# VCO-Simple-Back.net
KiCad netlist of a schematic drawn in EAGLE
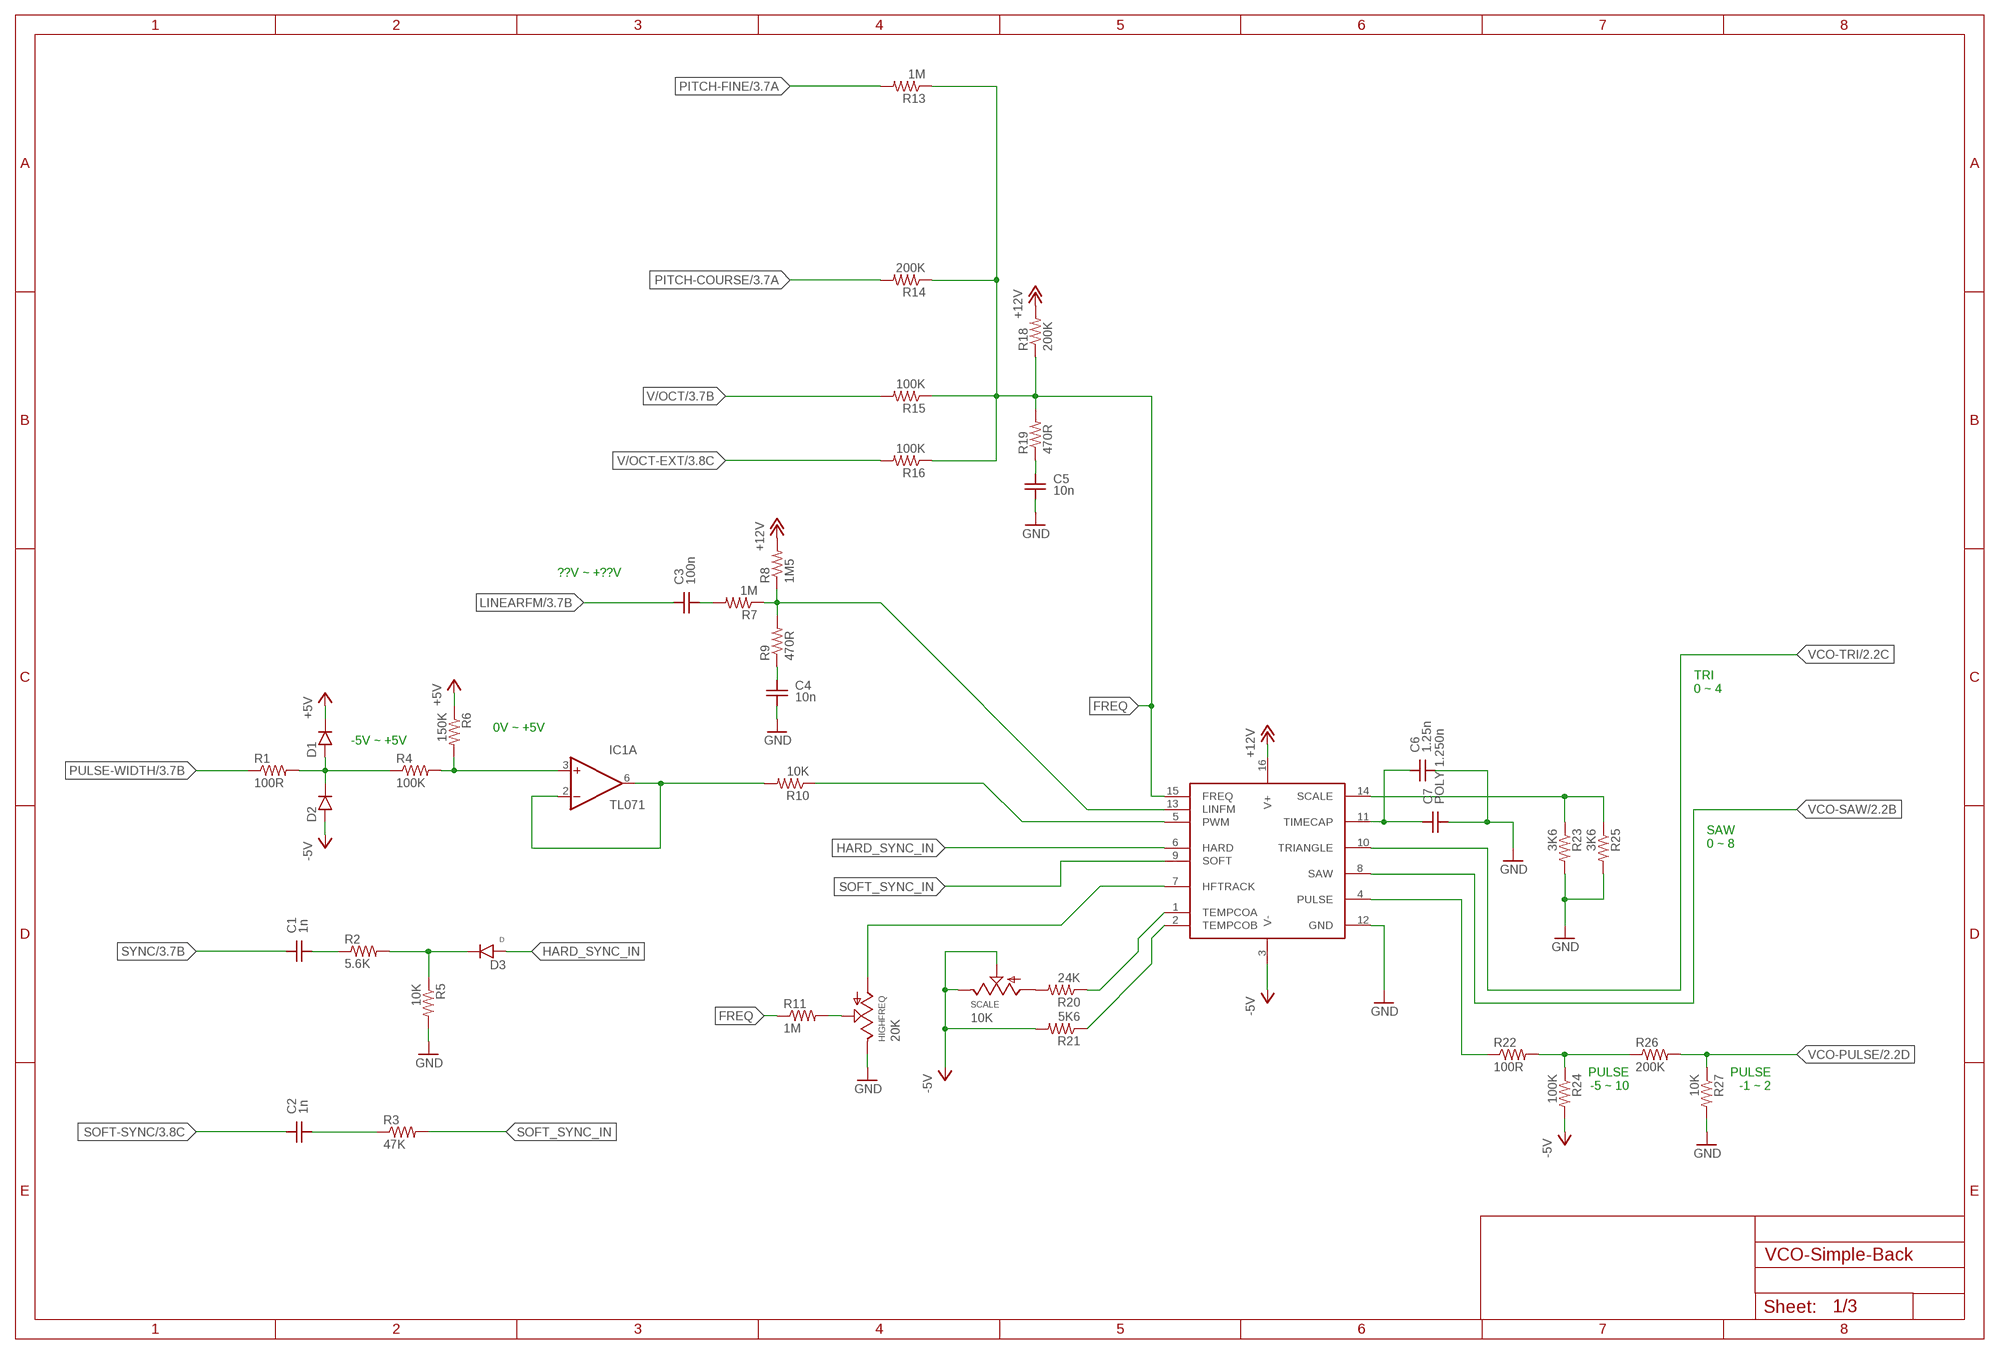
[diagram p0: schematic, sheet 1]
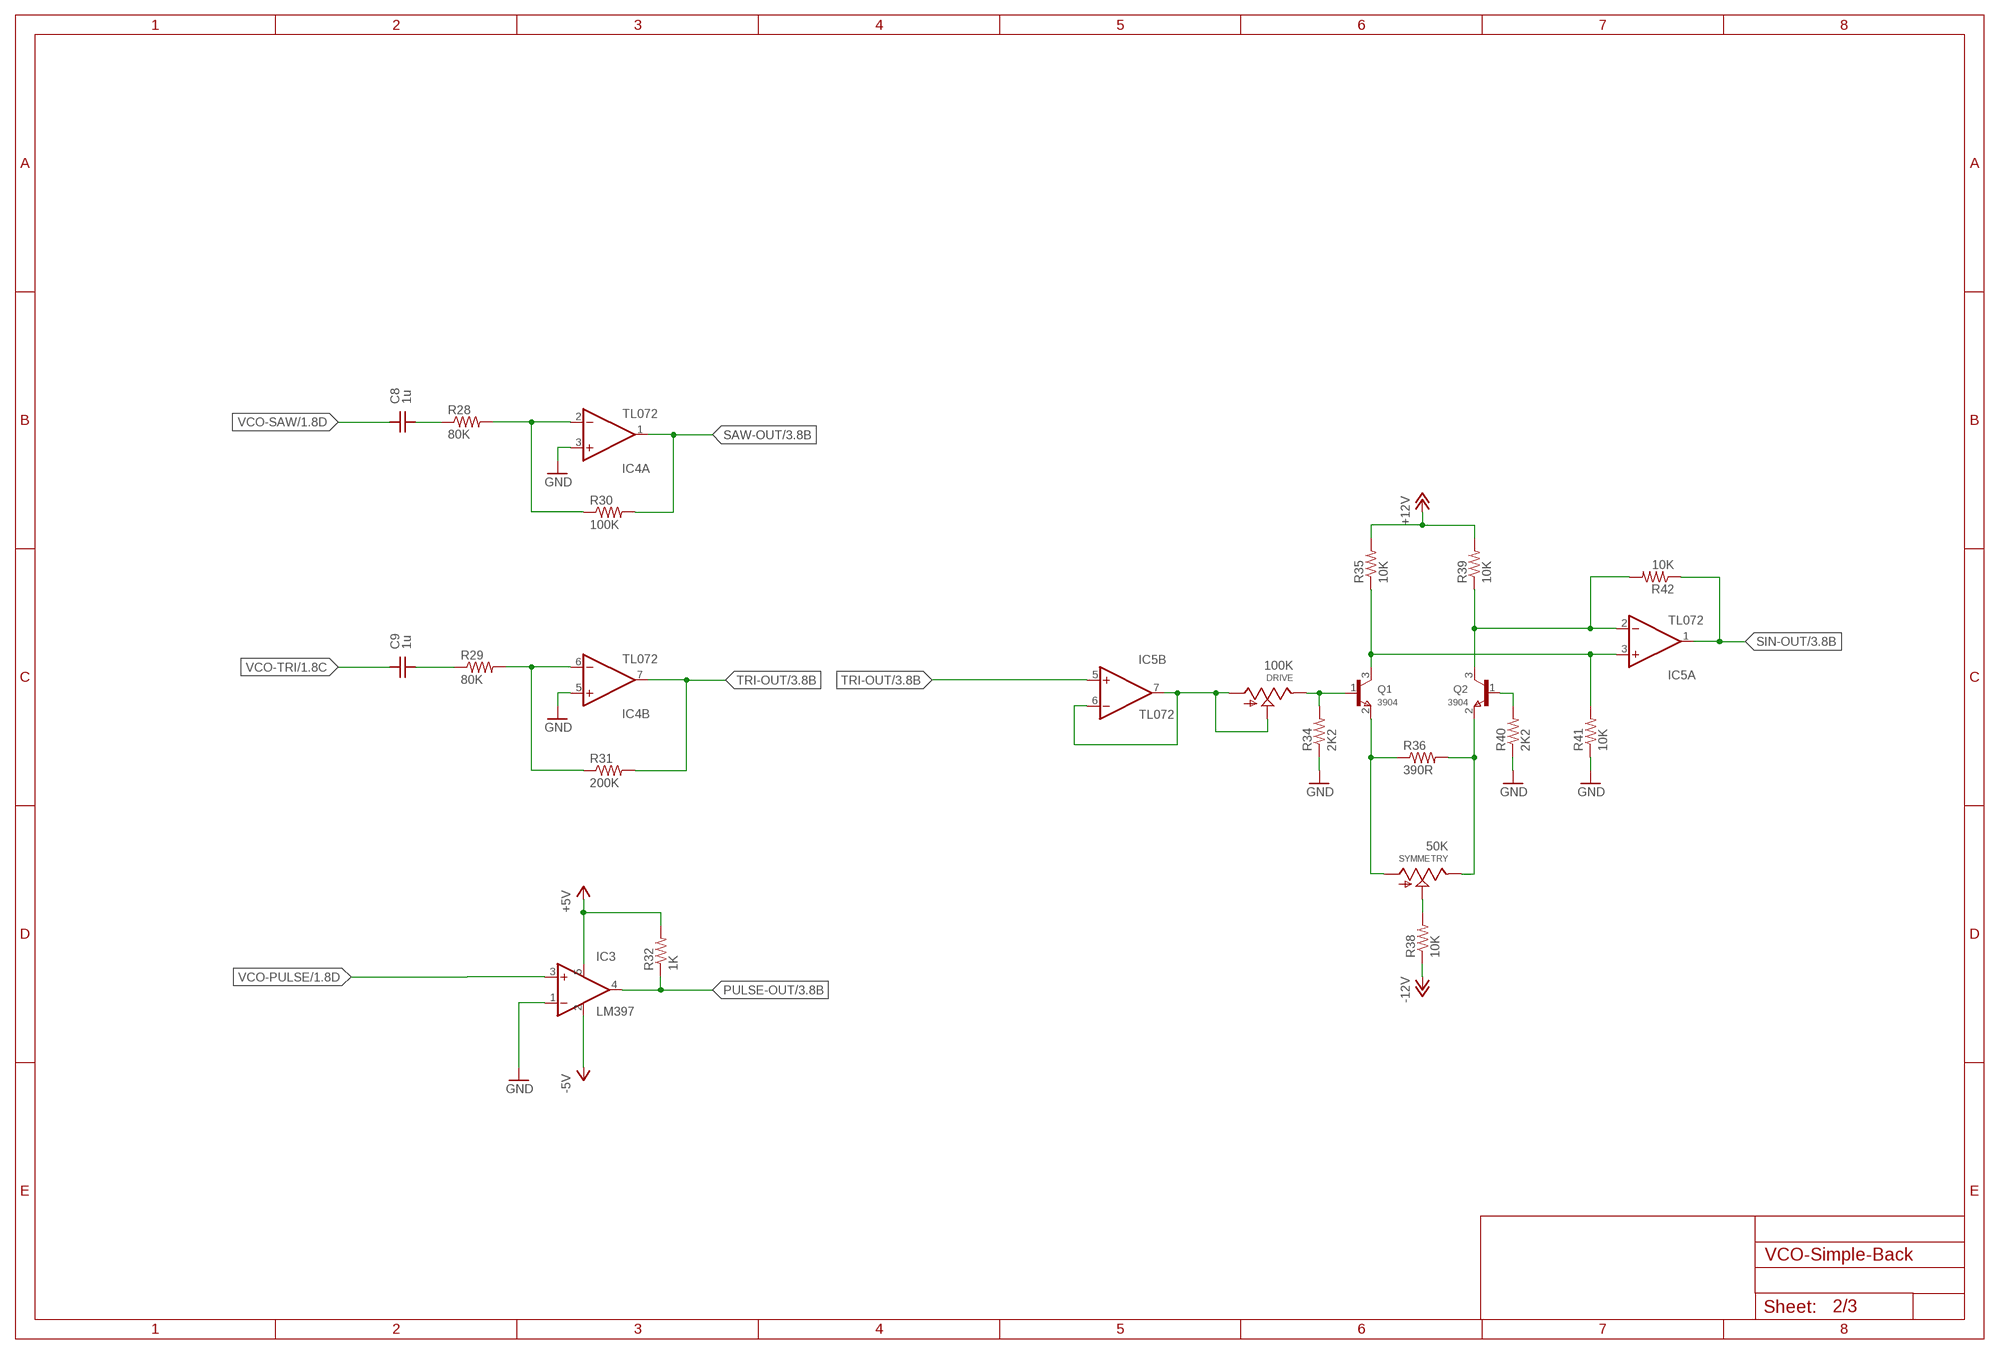
[diagram p1: schematic, sheet 2]
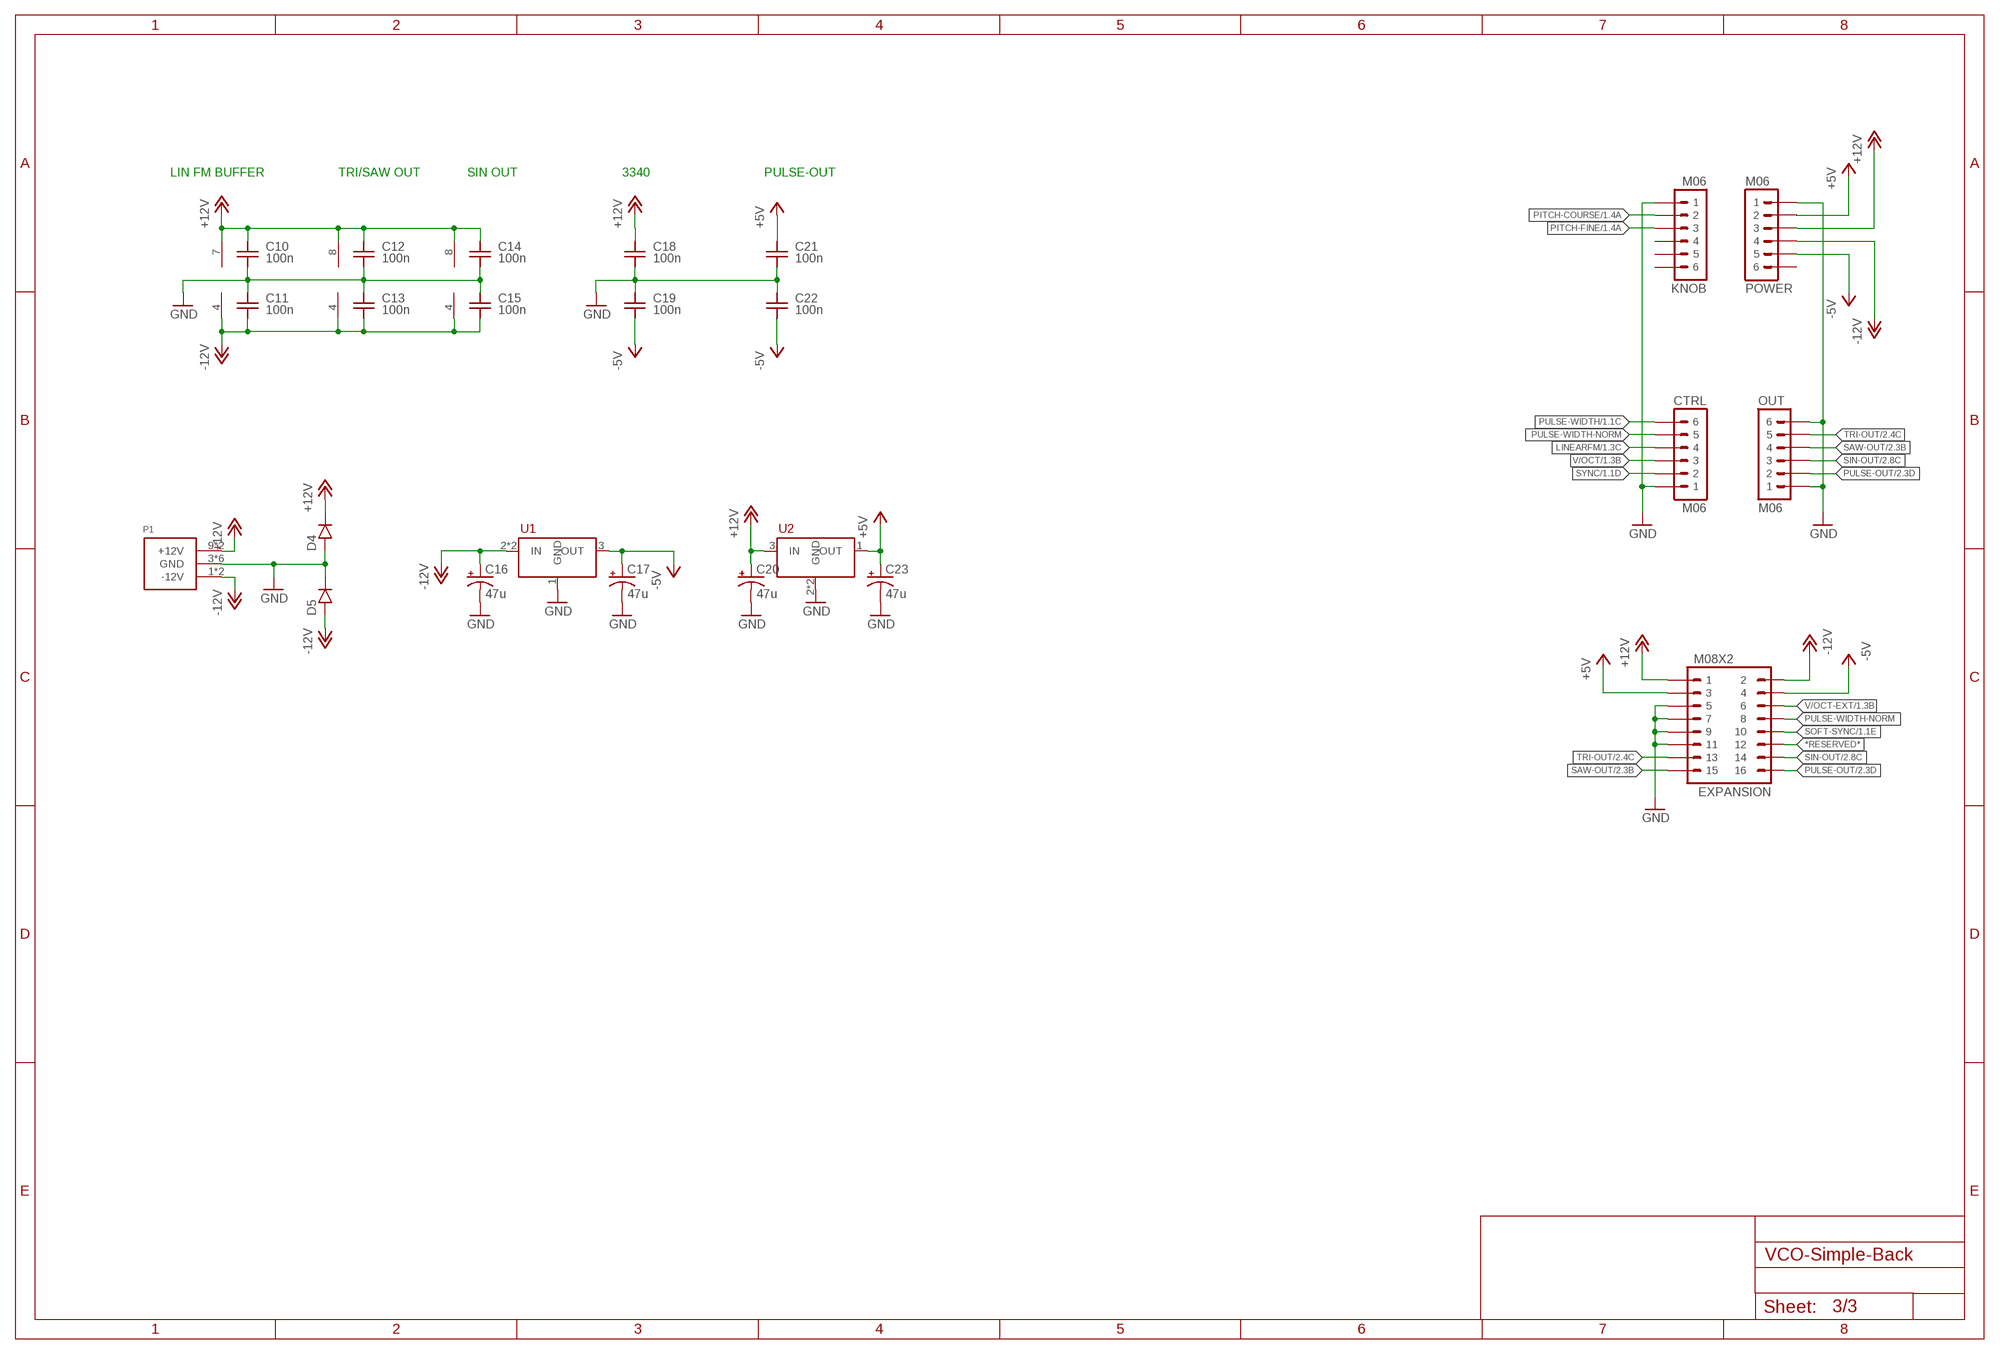
[diagram p2: schematic, sheet 3]

(export (version "E")
  (design (tool "Eeschema 10.0.6"))
  (components
    (comp (ref "C10")
      (value "100n")
      (footprint "eagle-import:C-0805")
      (libsource (lib "eagle-import") (part "CAPACITOR0805"))
    )
    (comp (ref "C11")
      (value "100n")
      (footprint "eagle-import:C-0805")
      (libsource (lib "eagle-import") (part "CAPACITOR0805"))
    )
    (comp (ref "C12")
      (value "100n")
      (footprint "eagle-import:C-0805")
      (libsource (lib "eagle-import") (part "CAPACITOR0805"))
    )
    (comp (ref "C13")
      (value "100n")
      (footprint "eagle-import:C-0805")
      (libsource (lib "eagle-import") (part "CAPACITOR0805"))
    )
    (comp (ref "C14")
      (value "100n")
      (footprint "eagle-import:C-0805")
      (libsource (lib "eagle-import") (part "CAPACITOR0805"))
    )
    (comp (ref "C15")
      (value "100n")
      (footprint "eagle-import:C-0805")
      (libsource (lib "eagle-import") (part "CAPACITOR0805"))
    )
    (comp (ref "C16")
      (value "47u")
      (footprint "eagle-import:PANASONIC_C")
      (libsource (lib "eagle-import") (part "CPOL-USC"))
    )
    (comp (ref "C17")
      (value "47u")
      (footprint "eagle-import:PANASONIC_C")
      (libsource (lib "eagle-import") (part "CPOL-USC"))
    )
    (comp (ref "C18")
      (value "100n")
      (footprint "eagle-import:C-0805")
      (libsource (lib "eagle-import") (part "CAPACITOR0805"))
    )
    (comp (ref "C19")
      (value "100n")
      (footprint "eagle-import:C-0805")
      (libsource (lib "eagle-import") (part "CAPACITOR0805"))
    )
    (comp (ref "C20")
      (value "47u")
      (footprint "eagle-import:PANASONIC_C")
      (libsource (lib "eagle-import") (part "CPOL-USC"))
    )
    (comp (ref "C21")
      (value "100n")
      (footprint "eagle-import:C-0805")
      (libsource (lib "eagle-import") (part "CAPACITOR0805"))
    )
    (comp (ref "C22")
      (value "100n")
      (footprint "eagle-import:C-0805")
      (libsource (lib "eagle-import") (part "CAPACITOR0805"))
    )
    (comp (ref "C23")
      (value "47u")
      (footprint "eagle-import:PANASONIC_C")
      (libsource (lib "eagle-import") (part "CPOL-USC"))
    )
    (comp (ref "CTRL")
      (value "M06")
      (footprint "eagle-import:M06")
      (libsource (lib "eagle-import") (part "M06"))
    )
    (comp (ref "D4")
      (value "DIODESOD-123")
      (footprint "eagle-import:SOD-123")
      (libsource (lib "eagle-import") (part "DIODESOD-123"))
    )
    (comp (ref "D5")
      (value "DIODESOD-123")
      (footprint "eagle-import:SOD-123")
      (libsource (lib "eagle-import") (part "DIODESOD-123"))
    )
    (comp (ref "EXPANSION")
      (value "M08X2")
      (footprint "eagle-import:M08X2")
      (libsource (lib "eagle-import") (part "M08X2"))
    )
    (comp (ref "IC1")
      (value "TL071")
      (footprint "eagle-import:SO08")
      (libsource (lib "eagle-import") (part "OPAMP-SINGLE"))
    )
    (comp (ref "IC4")
      (value "TL072")
      (footprint "eagle-import:SO08")
      (libsource (lib "eagle-import") (part "OPAMP-DUAL"))
    )
    (comp (ref "IC5")
      (value "TL072")
      (footprint "eagle-import:SO08")
      (libsource (lib "eagle-import") (part "OPAMP-DUAL"))
    )
    (comp (ref "KNOB")
      (value "M06")
      (footprint "eagle-import:M06")
      (libsource (lib "eagle-import") (part "M06"))
    )
    (comp (ref "OUT")
      (value "M06")
      (footprint "eagle-import:M06")
      (libsource (lib "eagle-import") (part "M06"))
    )
    (comp (ref "P1")
      (value "POWER_SIMPLE10_SHROUDED")
      (footprint "eagle-import:POWER_10_SHROUDED")
      (libsource (lib "eagle-import") (part "POWER_SIMPLE10_SHROUDED"))
    )
    (comp (ref "POWER")
      (value "M06")
      (footprint "eagle-import:M06")
      (libsource (lib "eagle-import") (part "M06"))
    )
    (comp (ref "U1")
      (value "LM79L05A")
      (footprint "eagle-import:SOT89")
      (libsource (lib "eagle-import") (part "LM79L05A"))
    )
    (comp (ref "U2")
      (value "MC78L05A")
      (footprint "eagle-import:SOT89")
      (libsource (lib "eagle-import") (part "MC78L05A"))
    )
    (comp (ref "C1")
      (value "1n")
      (footprint "eagle-import:C-0805")
      (libsource (lib "eagle-import") (part "CAPACITOR0805"))
    )
    (comp (ref "C2")
      (value "1n")
      (footprint "eagle-import:C-0805")
      (libsource (lib "eagle-import") (part "CAPACITOR0805"))
    )
    (comp (ref "C3")
      (value "100n")
      (footprint "eagle-import:C-0805")
      (libsource (lib "eagle-import") (part "CAPACITOR0805"))
    )
    (comp (ref "C4")
      (value "10n")
      (footprint "eagle-import:C-0805")
      (libsource (lib "eagle-import") (part "CAPACITOR0805"))
    )
    (comp (ref "C5")
      (value "10n")
      (footprint "eagle-import:C-0805")
      (libsource (lib "eagle-import") (part "CAPACITOR0805"))
    )
    (comp (ref "C6")
      (value "1.25n")
      (footprint "eagle-import:C-0805")
      (libsource (lib "eagle-import") (part "CAPACITOR0805"))
    )
    (comp (ref "C7")
      (value "POLY 1.250n")
      (footprint "eagle-import:CAP-5MM")
      (libsource (lib "eagle-import") (part "CAPACITOR5MM"))
    )
    (comp (ref "D1")
      (value "DIODESOD-323")
      (footprint "eagle-import:SOD-323")
      (libsource (lib "eagle-import") (part "DIODESOD-323"))
    )
    (comp (ref "D2")
      (value "DIODESOD-323")
      (footprint "eagle-import:SOD-323")
      (libsource (lib "eagle-import") (part "DIODESOD-323"))
    )
    (comp (ref "D3")
      (value "D")
      (footprint "eagle-import:SOD-323")
      (libsource (lib "eagle-import") (part "DIODESOD-323"))
    )
    (comp (ref "HIGHFREQ")
      (value "20K")
      (footprint "eagle-import:POT-TRIM-MULTI-V")
      (libsource (lib "eagle-import") (part "POTTRIM-MULTITURN-VERT"))
    )
    (comp (ref "IC2")
      (value "V3340SO16")
      (footprint "eagle-import:SO16")
      (libsource (lib "eagle-import") (part "V3340SO16"))
    )
    (comp (ref "R1")
      (value "100R")
      (footprint "eagle-import:R-0805-MILL")
      (libsource (lib "eagle-import") (part "RESISTOR0805"))
    )
    (comp (ref "R2")
      (value "5.6K")
      (footprint "eagle-import:R-0805-MILL")
      (libsource (lib "eagle-import") (part "RESISTOR0805"))
    )
    (comp (ref "R3")
      (value "47K")
      (footprint "eagle-import:R-0805-MILL")
      (libsource (lib "eagle-import") (part "RESISTOR0805"))
    )
    (comp (ref "R4")
      (value "100K")
      (footprint "eagle-import:R-0805-MILL")
      (libsource (lib "eagle-import") (part "RESISTOR0805"))
    )
    (comp (ref "R5")
      (value "10K")
      (footprint "eagle-import:R-0805-MILL")
      (libsource (lib "eagle-import") (part "RESISTOR0805"))
    )
    (comp (ref "R6")
      (value "150K")
      (footprint "eagle-import:R-0805-MILL")
      (libsource (lib "eagle-import") (part "RESISTOR0805"))
    )
    (comp (ref "R7")
      (value "1M")
      (footprint "eagle-import:R-0805-MILL")
      (libsource (lib "eagle-import") (part "RESISTOR0805"))
    )
    (comp (ref "R8")
      (value "1M5")
      (footprint "eagle-import:R-0805-MILL")
      (libsource (lib "eagle-import") (part "RESISTOR0805"))
    )
    (comp (ref "R9")
      (value "470R")
      (footprint "eagle-import:R-0805-MILL")
      (libsource (lib "eagle-import") (part "RESISTOR0805"))
    )
    (comp (ref "R10")
      (value "10K")
      (footprint "eagle-import:R-0805-MILL")
      (libsource (lib "eagle-import") (part "RESISTOR0805"))
    )
    (comp (ref "R11")
      (value "1M")
      (footprint "eagle-import:R-0805-MILL")
      (libsource (lib "eagle-import") (part "RESISTOR0805"))
    )
    (comp (ref "R13")
      (value "1M")
      (footprint "eagle-import:R-0805-MILL")
      (libsource (lib "eagle-import") (part "RESISTOR0805"))
    )
    (comp (ref "R14")
      (value "200K")
      (footprint "eagle-import:R-0805-MILL")
      (libsource (lib "eagle-import") (part "RESISTOR0805"))
    )
    (comp (ref "R15")
      (value "100K")
      (footprint "eagle-import:R-0805-MILL")
      (libsource (lib "eagle-import") (part "RESISTOR0805"))
    )
    (comp (ref "R16")
      (value "100K")
      (footprint "eagle-import:R-0805-MILL")
      (libsource (lib "eagle-import") (part "RESISTOR0805"))
    )
    (comp (ref "R18")
      (value "200K")
      (footprint "eagle-import:R-0805-MILL")
      (libsource (lib "eagle-import") (part "RESISTOR0805"))
    )
    (comp (ref "R19")
      (value "470R")
      (footprint "eagle-import:R-0805-MILL")
      (libsource (lib "eagle-import") (part "RESISTOR0805"))
    )
    (comp (ref "R20")
      (value "24K")
      (footprint "eagle-import:R-0805-MILL")
      (libsource (lib "eagle-import") (part "RESISTOR0805"))
    )
    (comp (ref "R21")
      (value "5K6")
      (footprint "eagle-import:R-0805-MILL")
      (libsource (lib "eagle-import") (part "RESISTOR0805"))
    )
    (comp (ref "R22")
      (value "100R")
      (footprint "eagle-import:R-0805-MILL")
      (libsource (lib "eagle-import") (part "RESISTOR0805"))
    )
    (comp (ref "R23")
      (value "3K6")
      (footprint "eagle-import:R-0805-MILL")
      (libsource (lib "eagle-import") (part "RESISTOR0805"))
    )
    (comp (ref "R24")
      (value "100K")
      (footprint "eagle-import:R-0805-MILL")
      (libsource (lib "eagle-import") (part "RESISTOR0805"))
    )
    (comp (ref "R25")
      (value "3K6")
      (footprint "eagle-import:R-0805-MILL")
      (libsource (lib "eagle-import") (part "RESISTOR0805"))
    )
    (comp (ref "R26")
      (value "200K")
      (footprint "eagle-import:R-0805-MILL")
      (libsource (lib "eagle-import") (part "RESISTOR0805"))
    )
    (comp (ref "R27")
      (value "10K")
      (footprint "eagle-import:R-0805-MILL")
      (libsource (lib "eagle-import") (part "RESISTOR0805"))
    )
    (comp (ref "SCALE")
      (value "10K")
      (footprint "eagle-import:POT-TRIM-MULTI-V")
      (libsource (lib "eagle-import") (part "POTTRIM-MULTITURN-VERT"))
    )
    (comp (ref "C8")
      (value "1u")
      (footprint "eagle-import:C-0805")
      (libsource (lib "eagle-import") (part "CAPACITOR0805"))
    )
    (comp (ref "C9")
      (value "1u")
      (footprint "eagle-import:C-0805")
      (libsource (lib "eagle-import") (part "CAPACITOR0805"))
    )
    (comp (ref "DRIVE")
      (value "100K")
      (footprint "eagle-import:POT-TRIM-MULTI-V")
      (libsource (lib "eagle-import") (part "POTTRIM-MULTITURN-VERT"))
    )
    (comp (ref "IC3")
      (value "LM397")
      (footprint "eagle-import:SOT23-5")
      (libsource (lib "eagle-import") (part "LM397"))
    )
    (comp (ref "Q1")
      (value "3904")
      (footprint "eagle-import:SOT23")
      (libsource (lib "eagle-import") (part "TRANSISTOR-NPNMMBT3904"))
    )
    (comp (ref "Q2")
      (value "3904")
      (footprint "eagle-import:SOT23")
      (libsource (lib "eagle-import") (part "TRANSISTOR-NPNMMBT3904"))
    )
    (comp (ref "R28")
      (value "80K")
      (footprint "eagle-import:R-0805-MILL")
      (libsource (lib "eagle-import") (part "RESISTOR0805"))
    )
    (comp (ref "R29")
      (value "80K")
      (footprint "eagle-import:R-0805-MILL")
      (libsource (lib "eagle-import") (part "RESISTOR0805"))
    )
    (comp (ref "R30")
      (value "100K")
      (footprint "eagle-import:R-0805-MILL")
      (libsource (lib "eagle-import") (part "RESISTOR0805"))
    )
    (comp (ref "R31")
      (value "200K")
      (footprint "eagle-import:R-0805-MILL")
      (libsource (lib "eagle-import") (part "RESISTOR0805"))
    )
    (comp (ref "R32")
      (value "1K")
      (footprint "eagle-import:R-0805-MILL")
      (libsource (lib "eagle-import") (part "RESISTOR0805"))
    )
    (comp (ref "R34")
      (value "2K2")
      (footprint "eagle-import:R-0805-MILL")
      (libsource (lib "eagle-import") (part "RESISTOR0805"))
    )
    (comp (ref "R35")
      (value "10K")
      (footprint "eagle-import:R-0805-MILL")
      (libsource (lib "eagle-import") (part "RESISTOR0805"))
    )
    (comp (ref "R36")
      (value "390R")
      (footprint "eagle-import:R-0805-MILL")
      (libsource (lib "eagle-import") (part "RESISTOR0805"))
    )
    (comp (ref "R38")
      (value "10K")
      (footprint "eagle-import:R-0805-MILL")
      (libsource (lib "eagle-import") (part "RESISTOR0805"))
    )
    (comp (ref "R39")
      (value "10K")
      (footprint "eagle-import:R-0805-MILL")
      (libsource (lib "eagle-import") (part "RESISTOR0805"))
    )
    (comp (ref "R40")
      (value "2K2")
      (footprint "eagle-import:R-0805-MILL")
      (libsource (lib "eagle-import") (part "RESISTOR0805"))
    )
    (comp (ref "R41")
      (value "10K")
      (footprint "eagle-import:R-0805-MILL")
      (libsource (lib "eagle-import") (part "RESISTOR0805"))
    )
    (comp (ref "R42")
      (value "10K")
      (footprint "eagle-import:R-0805-MILL")
      (libsource (lib "eagle-import") (part "RESISTOR0805"))
    )
    (comp (ref "SYMMETRY")
      (value "50K")
      (footprint "eagle-import:POT-TRIM-MULTI-V")
      (libsource (lib "eagle-import") (part "POTTRIM-MULTITURN-VERT"))
    )
  )
  (nets
    (net (code "1") (name "*RESERVED*") (class "Default")
      (node (ref "EXPANSION") (pin "12") (pinfunction "12_12") (pintype "passive"))
    )
    (net (code "2") (name "+5V") (class "Default")
      (node (ref "C21") (pin "1") (pinfunction "1_1") (pintype "passive"))
      (node (ref "C23") (pin "+") (pinfunction "+_+") (pintype "passive"))
      (node (ref "D1") (pin "K") (pinfunction "C_K") (pintype "passive"))
      (node (ref "EXPANSION") (pin "3") (pinfunction "3_3") (pintype "passive"))
      (node (ref "IC3") (pin "5") (pinfunction "V+_5") (pintype "power_in"))
      (node (ref "POWER") (pin "2") (pinfunction "2_2") (pintype "passive"))
      (node (ref "R32") (pin "P$2") (pinfunction "2_P$2") (pintype "passive"))
      (node (ref "R6") (pin "P$1") (pinfunction "1_P$1") (pintype "passive"))
      (node (ref "U2") (pin "1") (pinfunction "OUT_1") (pintype "bidirectional"))
    )
    (net (code "3") (name "+12V") (class "Default")
      (node (ref "C10") (pin "1") (pinfunction "1_1") (pintype "passive"))
      (node (ref "C12") (pin "1") (pinfunction "1_1") (pintype "passive"))
      (node (ref "C14") (pin "1") (pinfunction "1_1") (pintype "passive"))
      (node (ref "C18") (pin "1") (pinfunction "1_1") (pintype "passive"))
      (node (ref "C20") (pin "+") (pinfunction "+_+") (pintype "passive"))
      (node (ref "D4") (pin "K") (pinfunction "C_K") (pintype "passive"))
      (node (ref "EXPANSION") (pin "1") (pinfunction "1_1") (pintype "passive"))
      (node (ref "IC1") (pin "7") (pinfunction "V+_7") (pintype "power_in"))
      (node (ref "IC2") (pin "16") (pinfunction "V+_16") (pintype "power_in"))
      (node (ref "IC4") (pin "8") (pinfunction "V+_8") (pintype "power_in"))
      (node (ref "IC5") (pin "8") (pinfunction "V+_8") (pintype "power_in"))
      (node (ref "P1") (pin "10") (pinfunction "+12V_10") (pintype "bidirectional"))
      (node (ref "P1") (pin "9") (pinfunction "+12V_9") (pintype "bidirectional"))
      (node (ref "POWER") (pin "3") (pinfunction "3_3") (pintype "passive"))
      (node (ref "R18") (pin "P$2") (pinfunction "2_P$2") (pintype "passive"))
      (node (ref "R35") (pin "P$2") (pinfunction "2_P$2") (pintype "passive"))
      (node (ref "R39") (pin "P$2") (pinfunction "2_P$2") (pintype "passive"))
      (node (ref "R8") (pin "P$2") (pinfunction "2_P$2") (pintype "passive"))
      (node (ref "U2") (pin "3") (pinfunction "IN_3") (pintype "bidirectional"))
    )
    (net (code "4") (name "-5V") (class "Default")
      (node (ref "C17") (pin "+") (pinfunction "+_+") (pintype "passive"))
      (node (ref "C19") (pin "2") (pinfunction "2_2") (pintype "passive"))
      (node (ref "C22") (pin "2") (pinfunction "2_2") (pintype "passive"))
      (node (ref "D2") (pin "A") (pinfunction "A_A") (pintype "passive"))
      (node (ref "EXPANSION") (pin "4") (pinfunction "4_4") (pintype "passive"))
      (node (ref "IC2") (pin "3") (pinfunction "V-_3") (pintype "bidirectional"))
      (node (ref "IC3") (pin "2") (pinfunction "GND_2") (pintype "power_in"))
      (node (ref "POWER") (pin "5") (pinfunction "5_5") (pintype "passive"))
      (node (ref "R21") (pin "P$2") (pinfunction "2_P$2") (pintype "passive"))
      (node (ref "R24") (pin "P$2") (pinfunction "2_P$2") (pintype "passive"))
      (node (ref "SCALE") (pin "B") (pinfunction "E_B") (pintype "passive"))
      (node (ref "SCALE") (pin "W") (pinfunction "S_W") (pintype "passive"))
      (node (ref "U1") (pin "3") (pinfunction "OUT_3") (pintype "bidirectional"))
    )
    (net (code "5") (name "-12V") (class "Default")
      (node (ref "C11") (pin "2") (pinfunction "2_2") (pintype "passive"))
      (node (ref "C13") (pin "2") (pinfunction "2_2") (pintype "passive"))
      (node (ref "C15") (pin "2") (pinfunction "2_2") (pintype "passive"))
      (node (ref "C16") (pin "+") (pinfunction "+_+") (pintype "passive"))
      (node (ref "D5") (pin "A") (pinfunction "A_A") (pintype "passive"))
      (node (ref "EXPANSION") (pin "2") (pinfunction "2_2") (pintype "passive"))
      (node (ref "IC1") (pin "4") (pinfunction "V-_4") (pintype "power_in"))
      (node (ref "IC4") (pin "4") (pinfunction "V-_4") (pintype "power_in"))
      (node (ref "IC5") (pin "4") (pinfunction "V-_4") (pintype "power_in"))
      (node (ref "P1") (pin "1") (pinfunction "-12V_1") (pintype "bidirectional"))
      (node (ref "P1") (pin "2") (pinfunction "-12V_2") (pintype "bidirectional"))
      (node (ref "POWER") (pin "4") (pinfunction "4_4") (pintype "passive"))
      (node (ref "R38") (pin "P$1") (pinfunction "1_P$1") (pintype "passive"))
      (node (ref "U1") (pin "2") (pinfunction "IN_2") (pintype "bidirectional"))
      (node (ref "U1") (pin "2B") (pinfunction "IN_2B") (pintype "bidirectional"))
    )
    (net (code "6") (name "FREQ") (class "Default")
      (node (ref "IC2") (pin "15") (pinfunction "FREQ_15") (pintype "bidirectional"))
      (node (ref "R11") (pin "P$1") (pinfunction "1_P$1") (pintype "passive"))
      (node (ref "R13") (pin "P$1") (pinfunction "1_P$1") (pintype "passive"))
      (node (ref "R14") (pin "P$1") (pinfunction "1_P$1") (pintype "passive"))
      (node (ref "R15") (pin "P$1") (pinfunction "1_P$1") (pintype "passive"))
      (node (ref "R16") (pin "P$1") (pinfunction "1_P$1") (pintype "passive"))
      (node (ref "R18") (pin "P$1") (pinfunction "1_P$1") (pintype "passive"))
      (node (ref "R19") (pin "P$2") (pinfunction "2_P$2") (pintype "passive"))
    )
    (net (code "7") (name "GND") (class "Default")
      (node (ref "C10") (pin "2") (pinfunction "2_2") (pintype "passive"))
      (node (ref "C11") (pin "1") (pinfunction "1_1") (pintype "passive"))
      (node (ref "C12") (pin "2") (pinfunction "2_2") (pintype "passive"))
      (node (ref "C13") (pin "1") (pinfunction "1_1") (pintype "passive"))
      (node (ref "C14") (pin "2") (pinfunction "2_2") (pintype "passive"))
      (node (ref "C15") (pin "1") (pinfunction "1_1") (pintype "passive"))
      (node (ref "C16") (pin "-") (pinfunction "-_-") (pintype "passive"))
      (node (ref "C17") (pin "-") (pinfunction "-_-") (pintype "passive"))
      (node (ref "C18") (pin "2") (pinfunction "2_2") (pintype "passive"))
      (node (ref "C19") (pin "1") (pinfunction "1_1") (pintype "passive"))
      (node (ref "C20") (pin "-") (pinfunction "-_-") (pintype "passive"))
      (node (ref "C21") (pin "2") (pinfunction "2_2") (pintype "passive"))
      (node (ref "C22") (pin "1") (pinfunction "1_1") (pintype "passive"))
      (node (ref "C23") (pin "-") (pinfunction "-_-") (pintype "passive"))
      (node (ref "C4") (pin "2") (pinfunction "2_2") (pintype "passive"))
      (node (ref "C5") (pin "2") (pinfunction "2_2") (pintype "passive"))
      (node (ref "C6") (pin "2") (pinfunction "2_2") (pintype "passive"))
      (node (ref "C7") (pin "2") (pinfunction "2_2") (pintype "passive"))
      (node (ref "CTRL") (pin "1") (pinfunction "1_1") (pintype "passive"))
      (node (ref "D4") (pin "A") (pinfunction "A_A") (pintype "passive"))
      (node (ref "D5") (pin "K") (pinfunction "C_K") (pintype "passive"))
      (node (ref "EXPANSION") (pin "11") (pinfunction "11_11") (pintype "passive"))
      (node (ref "EXPANSION") (pin "5") (pinfunction "5_5") (pintype "passive"))
      (node (ref "EXPANSION") (pin "7") (pinfunction "7_7") (pintype "passive"))
      (node (ref "EXPANSION") (pin "9") (pinfunction "9_9") (pintype "passive"))
      (node (ref "HIGHFREQ") (pin "B") (pinfunction "E_B") (pintype "passive"))
      (node (ref "IC2") (pin "12") (pinfunction "GND_12") (pintype "power_in"))
      (node (ref "IC3") (pin "1") (pinfunction "-IN_1") (pintype "input"))
      (node (ref "IC4") (pin "3") (pinfunction "+IN_3") (pintype "input"))
      (node (ref "IC4") (pin "5") (pinfunction "+IN_5") (pintype "input"))
      (node (ref "KNOB") (pin "1") (pinfunction "1_1") (pintype "passive"))
      (node (ref "OUT") (pin "1") (pinfunction "1_1") (pintype "passive"))
      (node (ref "OUT") (pin "6") (pinfunction "6_6") (pintype "passive"))
      (node (ref "P1") (pin "3") (pinfunction "GND_3") (pintype "bidirectional"))
      (node (ref "P1") (pin "4") (pinfunction "GND_4") (pintype "bidirectional"))
      (node (ref "P1") (pin "5") (pinfunction "GND_5") (pintype "bidirectional"))
      (node (ref "P1") (pin "6") (pinfunction "GND_6") (pintype "bidirectional"))
      (node (ref "P1") (pin "7") (pinfunction "GND_7") (pintype "bidirectional"))
      (node (ref "P1") (pin "8") (pinfunction "GND_8") (pintype "bidirectional"))
      (node (ref "POWER") (pin "1") (pinfunction "1_1") (pintype "passive"))
      (node (ref "R23") (pin "P$2") (pinfunction "2_P$2") (pintype "passive"))
      (node (ref "R25") (pin "P$2") (pinfunction "2_P$2") (pintype "passive"))
      (node (ref "R27") (pin "P$2") (pinfunction "2_P$2") (pintype "passive"))
      (node (ref "R34") (pin "P$1") (pinfunction "1_P$1") (pintype "passive"))
      (node (ref "R40") (pin "P$1") (pinfunction "1_P$1") (pintype "passive"))
      (node (ref "R41") (pin "P$1") (pinfunction "1_P$1") (pintype "passive"))
      (node (ref "R5") (pin "P$2") (pinfunction "2_P$2") (pintype "passive"))
      (node (ref "U1") (pin "1") (pinfunction "GND_1") (pintype "bidirectional"))
      (node (ref "U2") (pin "2") (pinfunction "GND_2") (pintype "bidirectional"))
      (node (ref "U2") (pin "2B") (pinfunction "GND_2B") (pintype "bidirectional"))
    )
    (net (code "8") (name "HARD_SYNC_IN") (class "Default")
      (node (ref "D3") (pin "A") (pinfunction "A_A") (pintype "passive"))
      (node (ref "IC2") (pin "6") (pinfunction "HARD_6") (pintype "bidirectional"))
    )
    (net (code "9") (name "LINEARFM") (class "Default")
      (node (ref "C3") (pin "1") (pinfunction "1_1") (pintype "passive"))
      (node (ref "CTRL") (pin "4") (pinfunction "4_4") (pintype "passive"))
    )
    (net (code "10") (name "Net-(D2-C)") (class "Default")
      (node (ref "D1") (pin "A") (pinfunction "A_A") (pintype "passive"))
      (node (ref "D2") (pin "K") (pinfunction "C_K") (pintype "passive"))
      (node (ref "R1") (pin "P$2") (pinfunction "2_P$2") (pintype "passive"))
      (node (ref "R4") (pin "P$1") (pinfunction "1_P$1") (pintype "passive"))
    )
    (net (code "11") (name "Net-(D3-C)") (class "Default")
      (node (ref "D3") (pin "K") (pinfunction "C_K") (pintype "passive"))
      (node (ref "R2") (pin "P$2") (pinfunction "2_P$2") (pintype "passive"))
      (node (ref "R5") (pin "P$1") (pinfunction "1_P$1") (pintype "passive"))
    )
    (net (code "12") (name "Net-(DRIVE-E)") (class "Default")
      (node (ref "DRIVE") (pin "B") (pinfunction "E_B") (pintype "passive"))
      (node (ref "Q1") (pin "1") (pinfunction "B_1") (pintype "passive"))
      (node (ref "R34") (pin "P$2") (pinfunction "2_P$2") (pintype "passive"))
    )
    (net (code "13") (name "Net-(DRIVE-S)") (class "Default")
      (node (ref "DRIVE") (pin "A") (pinfunction "A_A") (pintype "passive"))
      (node (ref "DRIVE") (pin "W") (pinfunction "S_W") (pintype "passive"))
      (node (ref "IC5") (pin "6") (pinfunction "-IN_6") (pintype "input"))
      (node (ref "IC5") (pin "7") (pinfunction "OUT_7") (pintype "output"))
    )
    (net (code "14") (name "Net-(HIGHFREQ-S)") (class "Default")
      (node (ref "HIGHFREQ") (pin "W") (pinfunction "S_W") (pintype "passive"))
      (node (ref "R11") (pin "P$2") (pinfunction "2_P$2") (pintype "passive"))
    )
    (net (code "15") (name "Net-(IC1A-+IN)") (class "Default")
      (node (ref "IC1") (pin "3") (pinfunction "+IN_3") (pintype "input"))
      (node (ref "R4") (pin "P$2") (pinfunction "2_P$2") (pintype "passive"))
      (node (ref "R6") (pin "P$2") (pinfunction "2_P$2") (pintype "passive"))
    )
    (net (code "16") (name "Net-(IC1A--IN)") (class "Default")
      (node (ref "IC1") (pin "2") (pinfunction "-IN_2") (pintype "input"))
      (node (ref "IC1") (pin "6") (pinfunction "OUT_6") (pintype "output"))
      (node (ref "R10") (pin "P$2") (pinfunction "2_P$2") (pintype "passive"))
    )
    (net (code "17") (name "Net-(IC2-HFTRACK)") (class "Default")
      (node (ref "HIGHFREQ") (pin "A") (pinfunction "A_A") (pintype "passive"))
      (node (ref "IC2") (pin "7") (pinfunction "HFTRACK_7") (pintype "bidirectional"))
    )
    (net (code "18") (name "Net-(IC2-LINFM)") (class "Default")
      (node (ref "IC2") (pin "13") (pinfunction "LINFM_13") (pintype "bidirectional"))
      (node (ref "R7") (pin "P$1") (pinfunction "1_P$1") (pintype "passive"))
      (node (ref "R8") (pin "P$1") (pinfunction "1_P$1") (pintype "passive"))
      (node (ref "R9") (pin "P$2") (pinfunction "2_P$2") (pintype "passive"))
    )
    (net (code "19") (name "Net-(IC2-PULSE)") (class "Default")
      (node (ref "IC2") (pin "4") (pinfunction "PULSE_4") (pintype "bidirectional"))
      (node (ref "R22") (pin "P$1") (pinfunction "1_P$1") (pintype "passive"))
    )
    (net (code "20") (name "Net-(IC2-PWM)") (class "Default")
      (node (ref "IC2") (pin "5") (pinfunction "PWM_5") (pintype "bidirectional"))
      (node (ref "R10") (pin "P$1") (pinfunction "1_P$1") (pintype "passive"))
    )
    (net (code "21") (name "Net-(IC2-SCALE)") (class "Default")
      (node (ref "IC2") (pin "14") (pinfunction "SCALE_14") (pintype "bidirectional"))
      (node (ref "R23") (pin "P$1") (pinfunction "1_P$1") (pintype "passive"))
      (node (ref "R25") (pin "P$1") (pinfunction "1_P$1") (pintype "passive"))
    )
    (net (code "22") (name "Net-(IC2-TEMPCOA)") (class "Default")
      (node (ref "IC2") (pin "1") (pinfunction "TEMPCOA_1") (pintype "bidirectional"))
      (node (ref "R20") (pin "P$1") (pinfunction "1_P$1") (pintype "passive"))
    )
    (net (code "23") (name "Net-(IC2-TEMPCOB)") (class "Default")
      (node (ref "IC2") (pin "2") (pinfunction "TEMPCOB_2") (pintype "bidirectional"))
      (node (ref "R21") (pin "P$1") (pinfunction "1_P$1") (pintype "passive"))
    )
    (net (code "24") (name "Net-(IC2-TIMECAP)") (class "Default")
      (node (ref "C6") (pin "1") (pinfunction "1_1") (pintype "passive"))
      (node (ref "C7") (pin "1") (pinfunction "1_1") (pintype "passive"))
      (node (ref "IC2") (pin "11") (pinfunction "TIMECAP_11") (pintype "bidirectional"))
    )
    (net (code "25") (name "Net-(IC4A--IN)") (class "Default")
      (node (ref "IC4") (pin "2") (pinfunction "-IN_2") (pintype "input"))
      (node (ref "R28") (pin "P$2") (pinfunction "2_P$2") (pintype "passive"))
      (node (ref "R30") (pin "P$1") (pinfunction "1_P$1") (pintype "passive"))
    )
    (net (code "26") (name "Net-(IC4B--IN)") (class "Default")
      (node (ref "IC4") (pin "6") (pinfunction "-IN_6") (pintype "input"))
      (node (ref "R29") (pin "P$2") (pinfunction "2_P$2") (pintype "passive"))
      (node (ref "R31") (pin "P$1") (pinfunction "1_P$1") (pintype "passive"))
    )
    (net (code "27") (name "Net-(IC5A-+IN)") (class "Default")
      (node (ref "IC5") (pin "3") (pinfunction "+IN_3") (pintype "input"))
      (node (ref "Q1") (pin "3") (pinfunction "C_3") (pintype "passive"))
      (node (ref "R35") (pin "P$1") (pinfunction "1_P$1") (pintype "passive"))
      (node (ref "R41") (pin "P$2") (pinfunction "2_P$2") (pintype "passive"))
    )
    (net (code "28") (name "Net-(IC5A--IN)") (class "Default")
      (node (ref "IC5") (pin "2") (pinfunction "-IN_2") (pintype "input"))
      (node (ref "Q2") (pin "3") (pinfunction "C_3") (pintype "passive"))
      (node (ref "R39") (pin "P$1") (pinfunction "1_P$1") (pintype "passive"))
      (node (ref "R42") (pin "P$2") (pinfunction "2_P$2") (pintype "passive"))
    )
    (net (code "29") (name "Net-(Q1-E)") (class "Default")
      (node (ref "Q1") (pin "2") (pinfunction "E_2") (pintype "passive"))
      (node (ref "R36") (pin "P$1") (pinfunction "1_P$1") (pintype "passive"))
      (node (ref "SYMMETRY") (pin "A") (pinfunction "A_A") (pintype "passive"))
    )
    (net (code "30") (name "Net-(Q2-B)") (class "Default")
      (node (ref "Q2") (pin "1") (pinfunction "B_1") (pintype "passive"))
      (node (ref "R40") (pin "P$2") (pinfunction "2_P$2") (pintype "passive"))
    )
    (net (code "31") (name "Net-(Q2-E)") (class "Default")
      (node (ref "Q2") (pin "2") (pinfunction "E_2") (pintype "passive"))
      (node (ref "R36") (pin "P$2") (pinfunction "2_P$2") (pintype "passive"))
      (node (ref "SYMMETRY") (pin "B") (pinfunction "E_B") (pintype "passive"))
    )
    (net (code "32") (name "Net-(R2-1)") (class "Default")
      (node (ref "C1") (pin "2") (pinfunction "2_2") (pintype "passive"))
      (node (ref "R2") (pin "P$1") (pinfunction "1_P$1") (pintype "passive"))
    )
    (net (code "33") (name "Net-(R3-1)") (class "Default")
      (node (ref "C2") (pin "2") (pinfunction "2_2") (pintype "passive"))
      (node (ref "R3") (pin "P$1") (pinfunction "1_P$1") (pintype "passive"))
    )
    (net (code "34") (name "Net-(R7-2)") (class "Default")
      (node (ref "C3") (pin "2") (pinfunction "2_2") (pintype "passive"))
      (node (ref "R7") (pin "P$2") (pinfunction "2_P$2") (pintype "passive"))
    )
    (net (code "35") (name "Net-(R9-1)") (class "Default")
      (node (ref "C4") (pin "1") (pinfunction "1_1") (pintype "passive"))
      (node (ref "R9") (pin "P$1") (pinfunction "1_P$1") (pintype "passive"))
    )
    (net (code "36") (name "Net-(R19-1)") (class "Default")
      (node (ref "C5") (pin "1") (pinfunction "1_1") (pintype "passive"))
      (node (ref "R19") (pin "P$1") (pinfunction "1_P$1") (pintype "passive"))
    )
    (net (code "37") (name "Net-(R20-2)") (class "Default")
      (node (ref "R20") (pin "P$2") (pinfunction "2_P$2") (pintype "passive"))
      (node (ref "SCALE") (pin "A") (pinfunction "A_A") (pintype "passive"))
    )
    (net (code "38") (name "Net-(R22-2)") (class "Default")
      (node (ref "R22") (pin "P$2") (pinfunction "2_P$2") (pintype "passive"))
      (node (ref "R24") (pin "P$1") (pinfunction "1_P$1") (pintype "passive"))
      (node (ref "R26") (pin "P$1") (pinfunction "1_P$1") (pintype "passive"))
    )
    (net (code "39") (name "Net-(R28-1)") (class "Default")
      (node (ref "C8") (pin "2") (pinfunction "2_2") (pintype "passive"))
      (node (ref "R28") (pin "P$1") (pinfunction "1_P$1") (pintype "passive"))
    )
    (net (code "40") (name "Net-(R29-1)") (class "Default")
      (node (ref "C9") (pin "2") (pinfunction "2_2") (pintype "passive"))
      (node (ref "R29") (pin "P$1") (pinfunction "1_P$1") (pintype "passive"))
    )
    (net (code "41") (name "Net-(R38-2)") (class "Default")
      (node (ref "R38") (pin "P$2") (pinfunction "2_P$2") (pintype "passive"))
      (node (ref "SYMMETRY") (pin "W") (pinfunction "S_W") (pintype "passive"))
    )
    (net (code "42") (name "PITCH-COURSE") (class "Default")
      (node (ref "KNOB") (pin "2") (pinfunction "2_2") (pintype "passive"))
      (node (ref "R14") (pin "P$2") (pinfunction "2_P$2") (pintype "passive"))
    )
    (net (code "43") (name "PITCH-FINE") (class "Default")
      (node (ref "KNOB") (pin "3") (pinfunction "3_3") (pintype "passive"))
      (node (ref "R13") (pin "P$2") (pinfunction "2_P$2") (pintype "passive"))
    )
    (net (code "44") (name "PULSE-OUT") (class "Default")
      (node (ref "EXPANSION") (pin "16") (pinfunction "16_16") (pintype "passive"))
      (node (ref "IC3") (pin "4") (pinfunction "OUT_4") (pintype "output"))
      (node (ref "OUT") (pin "2") (pinfunction "2_2") (pintype "passive"))
      (node (ref "R32") (pin "P$1") (pinfunction "1_P$1") (pintype "passive"))
    )
    (net (code "45") (name "PULSE-WIDTH") (class "Default")
      (node (ref "CTRL") (pin "6") (pinfunction "6_6") (pintype "passive"))
      (node (ref "R1") (pin "P$1") (pinfunction "1_P$1") (pintype "passive"))
    )
    (net (code "46") (name "PULSE-WIDTH-NORM") (class "Default")
      (node (ref "CTRL") (pin "5") (pinfunction "5_5") (pintype "passive"))
      (node (ref "EXPANSION") (pin "8") (pinfunction "8_8") (pintype "passive"))
    )
    (net (code "47") (name "SAW-OUT") (class "Default")
      (node (ref "EXPANSION") (pin "15") (pinfunction "15_15") (pintype "passive"))
      (node (ref "IC4") (pin "1") (pinfunction "OUT_1") (pintype "output"))
      (node (ref "OUT") (pin "4") (pinfunction "4_4") (pintype "passive"))
      (node (ref "R30") (pin "P$2") (pinfunction "2_P$2") (pintype "passive"))
    )
    (net (code "48") (name "SIN-OUT") (class "Default")
      (node (ref "EXPANSION") (pin "14") (pinfunction "14_14") (pintype "passive"))
      (node (ref "IC5") (pin "1") (pinfunction "OUT_1") (pintype "output"))
      (node (ref "OUT") (pin "3") (pinfunction "3_3") (pintype "passive"))
      (node (ref "R42") (pin "P$1") (pinfunction "1_P$1") (pintype "passive"))
    )
    (net (code "49") (name "SOFT-SYNC") (class "Default")
      (node (ref "C2") (pin "1") (pinfunction "1_1") (pintype "passive"))
      (node (ref "EXPANSION") (pin "10") (pinfunction "10_10") (pintype "passive"))
    )
    (net (code "50") (name "SOFT_SYNC_IN") (class "Default")
      (node (ref "IC2") (pin "9") (pinfunction "SOFT_9") (pintype "bidirectional"))
      (node (ref "R3") (pin "P$2") (pinfunction "2_P$2") (pintype "passive"))
    )
    (net (code "51") (name "SYNC") (class "Default")
      (node (ref "C1") (pin "1") (pinfunction "1_1") (pintype "passive"))
      (node (ref "CTRL") (pin "2") (pinfunction "2_2") (pintype "passive"))
    )
    (net (code "52") (name "TRI-OUT") (class "Default")
      (node (ref "EXPANSION") (pin "13") (pinfunction "13_13") (pintype "passive"))
      (node (ref "IC4") (pin "7") (pinfunction "OUT_7") (pintype "output"))
      (node (ref "IC5") (pin "5") (pinfunction "+IN_5") (pintype "input"))
      (node (ref "OUT") (pin "5") (pinfunction "5_5") (pintype "passive"))
      (node (ref "R31") (pin "P$2") (pinfunction "2_P$2") (pintype "passive"))
    )
    (net (code "53") (name "VCO-PULSE") (class "Default")
      (node (ref "IC3") (pin "3") (pinfunction "+IN_3") (pintype "input"))
      (node (ref "R26") (pin "P$2") (pinfunction "2_P$2") (pintype "passive"))
      (node (ref "R27") (pin "P$1") (pinfunction "1_P$1") (pintype "passive"))
    )
    (net (code "54") (name "VCO-SAW") (class "Default")
      (node (ref "C8") (pin "1") (pinfunction "1_1") (pintype "passive"))
      (node (ref "IC2") (pin "8") (pinfunction "SAW_8") (pintype "bidirectional"))
    )
    (net (code "55") (name "VCO-TRI") (class "Default")
      (node (ref "C9") (pin "1") (pinfunction "1_1") (pintype "passive"))
      (node (ref "IC2") (pin "10") (pinfunction "TRIANGLE_10") (pintype "bidirectional"))
    )
    (net (code "56") (name "V{slash}OCT") (class "Default")
      (node (ref "CTRL") (pin "3") (pinfunction "3_3") (pintype "passive"))
      (node (ref "R15") (pin "P$2") (pinfunction "2_P$2") (pintype "passive"))
    )
    (net (code "57") (name "V{slash}OCT-EXT") (class "Default")
      (node (ref "EXPANSION") (pin "6") (pinfunction "6_6") (pintype "passive"))
      (node (ref "R16") (pin "P$2") (pinfunction "2_P$2") (pintype "passive"))
    )
    (net (code "58") (name "unconnected-(KNOB-Pad4)") (class "Default")
      (node (ref "KNOB") (pin "4") (pinfunction "4_4") (pintype "passive"))
    )
    (net (code "59") (name "unconnected-(KNOB-Pad5)") (class "Default")
      (node (ref "KNOB") (pin "5") (pinfunction "5_5") (pintype "passive"))
    )
    (net (code "60") (name "unconnected-(KNOB-Pad6)") (class "Default")
      (node (ref "KNOB") (pin "6") (pinfunction "6_6") (pintype "passive"))
    )
    (net (code "61") (name "unconnected-(POWER-Pad6)") (class "Default")
      (node (ref "POWER") (pin "6") (pinfunction "6_6") (pintype "passive"))
    )
  )
)
